# Power_Control.net
KiCad netlist of a schematic drawn in Altium Designer
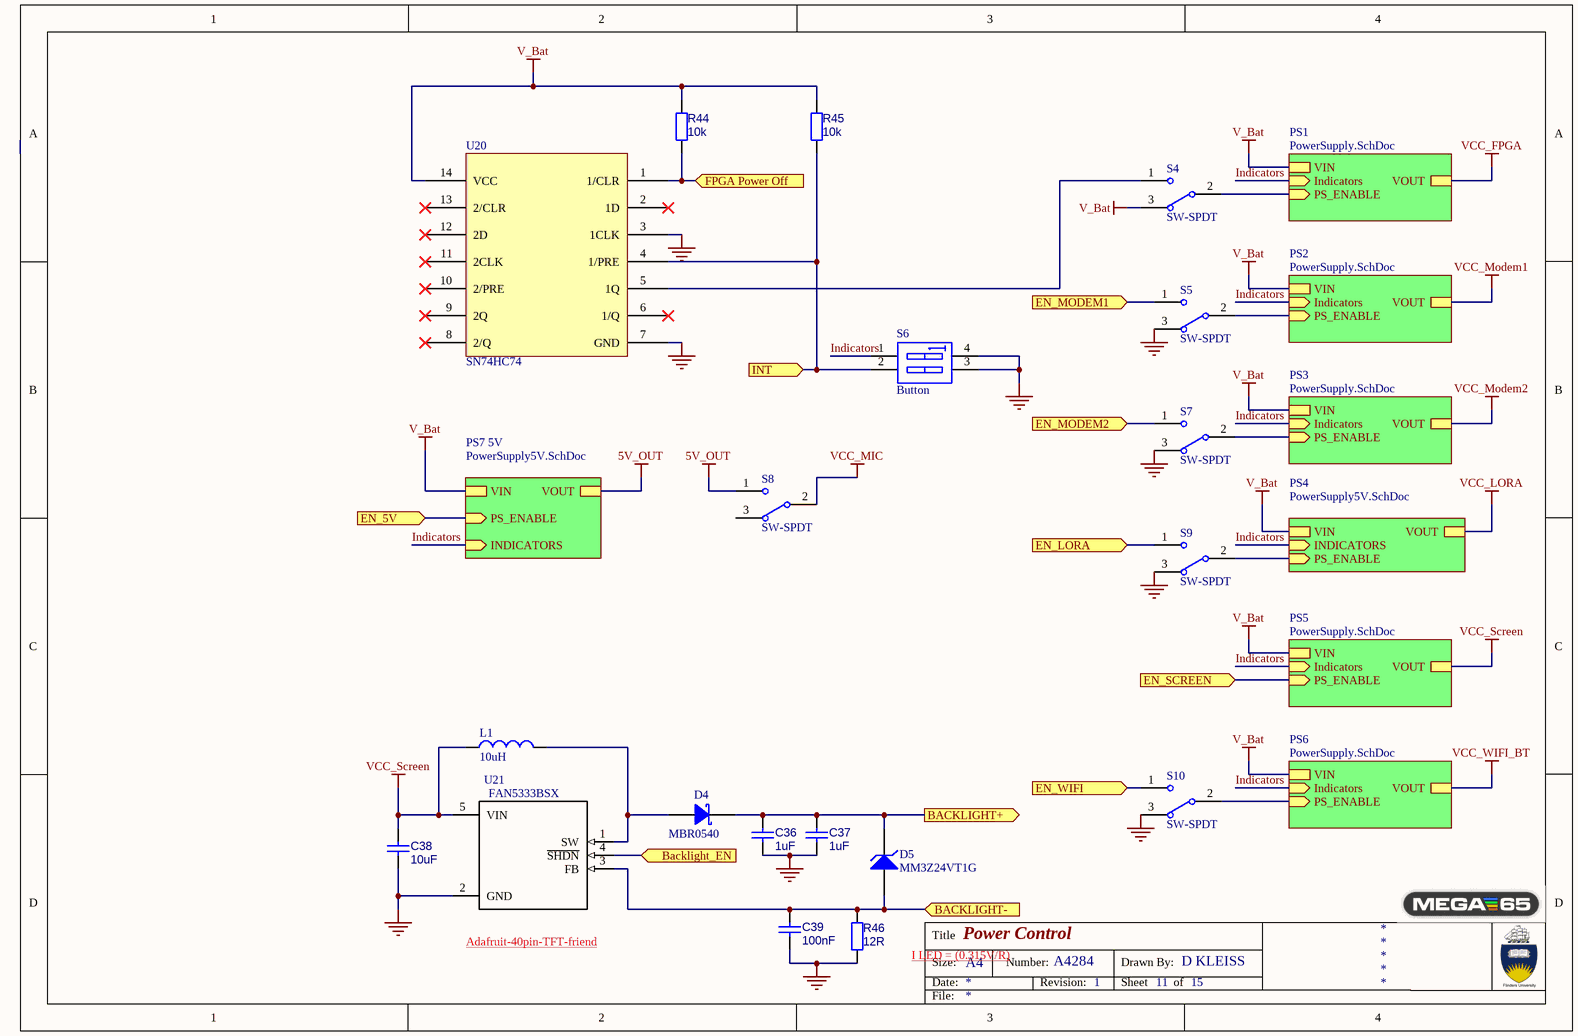
[diagram p0: Power Control.SchDoc]

(export (version "E")
  (design (tool "Eeschema 10.0.6"))
  (components
    (comp (ref "C36")
      (value "1uF")
      (footprint "0603_CAP UF HD")
      (description "Capacitor")
      (fields (field (name "MANUFACTURER") "Samsung"))
      (libsource (lib "Workshop Library 2010_06_24") (part "Cap"))
    )
    (comp (ref "C37")
      (value "1uF")
      (footprint "0603_CAP UF HD")
      (description "Capacitor")
      (fields (field (name "MANUFACTURER") "Samsung"))
      (libsource (lib "Workshop Library 2010_06_24") (part "Cap"))
    )
    (comp (ref "C38")
      (value "10uF")
      (footprint "0603_CAP UF HD")
      (description "Capacitor")
      (fields (field (name "MANUFACTURER") "Murata"))
      (libsource (lib "Workshop Library 2010_06_24") (part "Cap"))
    )
    (comp (ref "C39")
      (value "100nF")
      (footprint "0603_CAP UF HD")
      (description "Capacitor")
      (libsource (lib "Workshop Library 2010_06_24") (part "Cap"))
    )
    (comp (ref "D4")
      (value "MBR0540")
      (footprint "ONSC-SOD-123-2-425-04_V")
      (description "Diode")
      (fields (field (name "MANUFACTURER") "ON Semiconductor"))
      (libsource (lib "Workshop Library 2010_06_24") (part "DIODE_SCHOTTKY"))
    )
    (comp (ref "D5")
      (value "MM3Z24VT1G")
      (footprint "ONSC-SOD-323-2-477-02_V")
      (description "Zener Diode")
      (fields (field (name "MANUFACTURER") "ON Semiconductor"))
      (libsource (lib "Workshop Library 2010_06_24") (part "ZENER DIODE"))
    )
    (comp (ref "L1")
      (value "10uH")
      (footprint "TDK-SLF-6025-2_V")
      (description "Inductor")
      (fields (field (name "MANUFACTURER") "TDK"))
      (libsource (lib "Workshop Library 2010_06_24") (part "Inductor"))
    )
    (comp (ref "R44")
      (value "10k")
      (footprint "0603-RESISTOR HD")
      (description "Resistor")
      (libsource (lib "MEGAphone") (part "Resistor"))
    )
    (comp (ref "R45")
      (value "10k")
      (footprint "0603-RESISTOR HD")
      (description "Resistor")
      (libsource (lib "MEGAphone") (part "Resistor"))
    )
    (comp (ref "R46")
      (value "12R")
      (footprint "0805 Reflow")
      (description "Resistor")
      (libsource (lib "Workshop Library 2010_06_24") (part "Resistor"))
    )
    (comp (ref "S4")
      (value "SW-SPDT")
      (footprint "Switch SPDT OS102011MA1Q")
      (description "SPDT Subminiature Toggle Switch, Right Angle Mounting, Vertical Actuation")
      (fields
        (field (name "ELEMENT 14 PART NUMBER") "1201431")
        (field (name "MANUFACTURER") "C & K COMPONENTS")
      )
      (libsource (lib "Miscellaneous Devices") (part "SW-SPDT"))
    )
    (comp (ref "S5")
      (value "SW-SPDT")
      (footprint "Switch SPDT OS102011MA1Q")
      (description "SPDT Subminiature Toggle Switch, Right Angle Mounting, Vertical Actuation")
      (fields
        (field (name "ELEMENT 14 PART NUMBER") "1201431")
        (field (name "MANUFACTURER") "C & K COMPONENTS")
      )
      (libsource (lib "Miscellaneous Devices") (part "SW-SPDT"))
    )
    (comp (ref "S6")
      (value "Button")
      (footprint "Buttons Gameboy v2")
      (description "DIP Switch, 2 Position, SPST")
      (libsource (lib "Miscellaneous Devices") (part "SW DIP-2"))
    )
    (comp (ref "S7")
      (value "SW-SPDT")
      (footprint "Switch SPDT OS102011MA1Q")
      (description "SPDT Subminiature Toggle Switch, Right Angle Mounting, Vertical Actuation")
      (fields
        (field (name "ELEMENT 14 PART NUMBER") "1201431")
        (field (name "MANUFACTURER") "C & K COMPONENTS")
      )
      (libsource (lib "Miscellaneous Devices") (part "SW-SPDT"))
    )
    (comp (ref "S8")
      (value "SW-SPDT")
      (footprint "Switch SPDT OS102011MA1Q")
      (description "SPDT Subminiature Toggle Switch, Right Angle Mounting, Vertical Actuation")
      (fields
        (field (name "ELEMENT 14 PART NUMBER") "1201431")
        (field (name "MANUFACTURER") "C & K COMPONENTS")
      )
      (libsource (lib "Miscellaneous Devices") (part "SW-SPDT"))
    )
    (comp (ref "S9")
      (value "SW-SPDT")
      (footprint "Switch SPDT OS102011MA1Q")
      (description "SPDT Subminiature Toggle Switch, Right Angle Mounting, Vertical Actuation")
      (fields
        (field (name "ELEMENT 14 PART NUMBER") "1201431")
        (field (name "MANUFACTURER") "C & K COMPONENTS")
      )
      (libsource (lib "Miscellaneous Devices") (part "SW-SPDT"))
    )
    (comp (ref "S10")
      (value "SW-SPDT")
      (footprint "Switch SPDT OS102011MA1Q")
      (description "SPDT Subminiature Toggle Switch, Right Angle Mounting, Vertical Actuation")
      (fields
        (field (name "ELEMENT 14 PART NUMBER") "1201431")
        (field (name "MANUFACTURER") "C & K COMPONENTS")
      )
      (libsource (lib "Miscellaneous Devices") (part "SW-SPDT"))
    )
    (comp (ref "U20")
      (value "SN74HC74")
      (footprint "MEGAphone:SOIC-14")
      (fields (field (name "MANUFACTURER") "Texas Instruments"))
      (libsource (lib "MEGAphone") (part "SN74HC74"))
    )
    (comp (ref "U21")
      (value "FAN5333BSX")
      (footprint "SOT-23-5")
      (description "FAN5333B Series 5.5 V 1.5 MHz High Efficiency High Current Serial LED Driver")
      (fields (field (name "MANUFACTURER") "ON Semiconductor"))
      (libsource (lib "FAN5333BSX") (part "FAN5333BSX"))
    )
  )
  (nets
    (net (code "1") (name "/BACKLIGHT+") (class "Default")
      (node (ref "C36") (pin "1") (pinfunction "1_1") (pintype "passive"))
      (node (ref "C37") (pin "1") (pinfunction "1_1") (pintype "passive"))
      (node (ref "D4") (pin "2") (pinfunction "K_2") (pintype "passive"))
      (node (ref "D5") (pin "3") (pinfunction "K_3") (pintype "passive"))
    )
    (net (code "2") (name "/BACKLIGHT-") (class "Default")
      (node (ref "C39") (pin "1") (pinfunction "1_1") (pintype "passive"))
      (node (ref "D5") (pin "1") (pinfunction "A_1") (pintype "passive"))
      (node (ref "R46") (pin "1") (pinfunction "1_1") (pintype "passive"))
      (node (ref "U21") (pin "3") (pinfunction "FB_3") (pintype "input"))
    )
    (net (code "3") (name "/Backlight_EN") (class "Default")
      (node (ref "U21") (pin "4") (pinfunction "~{SHDN}_4") (pintype "input"))
    )
    (net (code "5") (name "/EN_LORA") (class "Default")
      (node (ref "S9") (pin "1") (pinfunction "1_1") (pintype "passive"))
    )
    (net (code "6") (name "/EN_MODEM1") (class "Default")
      (node (ref "S5") (pin "1") (pinfunction "1_1") (pintype "passive"))
    )
    (net (code "7") (name "/EN_MODEM2") (class "Default")
      (node (ref "S7") (pin "1") (pinfunction "1_1") (pintype "passive"))
    )
    (net (code "9") (name "/EN_WIFI") (class "Default")
      (node (ref "S10") (pin "1") (pinfunction "1_1") (pintype "passive"))
    )
    (net (code "10") (name "/FPGA Power Off") (class "Default")
      (node (ref "R44") (pin "2") (pinfunction "2_2") (pintype "passive"))
      (node (ref "U20") (pin "1") (pinfunction "1/CLR_1") (pintype "passive"))
    )
    (net (code "11") (name "/INT") (class "Default")
      (node (ref "R45") (pin "2") (pinfunction "2_2") (pintype "passive"))
      (node (ref "S6") (pin "2") (pinfunction "A2_2") (pintype "passive"))
      (node (ref "U20") (pin "4") (pinfunction "1/PRE_4") (pintype "passive"))
    )
    (net (code "12") (name "/Indicators") (class "Default")
      (node (ref "S6") (pin "1") (pinfunction "A1_1") (pintype "passive"))
    )
    (net (code "13") (name "/PS_ENABLE") (class "Default")
      (node (ref "S7") (pin "2") (pinfunction "2_2") (pintype "power_in"))
    )
    (net (code "14") (name "/PS_ENABLE_1") (class "Default")
      (node (ref "S10") (pin "2") (pinfunction "2_2") (pintype "power_in"))
    )
    (net (code "15") (name "/PS_ENABLE_2") (class "Default")
      (node (ref "S9") (pin "2") (pinfunction "2_2") (pintype "power_in"))
    )
    (net (code "16") (name "/PS_ENABLE_3") (class "Default")
      (node (ref "S5") (pin "2") (pinfunction "2_2") (pintype "power_in"))
    )
    (net (code "17") (name "/PS_ENABLE_4") (class "Default")
      (node (ref "S4") (pin "2") (pinfunction "2_2") (pintype "power_in"))
    )
    (net (code "18") (name "5V_OUT") (class "Default")
      (node (ref "S8") (pin "1") (pinfunction "1_1") (pintype "passive"))
    )
    (net (code "19") (name "GND") (class "Default")
      (node (ref "C36") (pin "2") (pinfunction "2_2") (pintype "passive"))
      (node (ref "C37") (pin "2") (pinfunction "2_2") (pintype "passive"))
      (node (ref "C38") (pin "2") (pinfunction "2_2") (pintype "passive"))
      (node (ref "C39") (pin "2") (pinfunction "2_2") (pintype "passive"))
      (node (ref "R46") (pin "2") (pinfunction "2_2") (pintype "passive"))
      (node (ref "S10") (pin "3") (pinfunction "3_3") (pintype "passive"))
      (node (ref "S5") (pin "3") (pinfunction "3_3") (pintype "passive"))
      (node (ref "S6") (pin "3") (pinfunction "B2_3") (pintype "passive"))
      (node (ref "S6") (pin "4") (pinfunction "B1_4") (pintype "passive"))
      (node (ref "S7") (pin "3") (pinfunction "3_3") (pintype "passive"))
      (node (ref "S9") (pin "3") (pinfunction "3_3") (pintype "passive"))
      (node (ref "U20") (pin "3") (pinfunction "1CLK_3") (pintype "passive"))
      (node (ref "U20") (pin "7") (pinfunction "GND_7") (pintype "passive"))
      (node (ref "U21") (pin "2") (pinfunction "GND_2") (pintype "power_in"))
    )
    (net (code "20") (name "Net-(D4-A)") (class "Default")
      (node (ref "D4") (pin "1") (pinfunction "A_1") (pintype "passive"))
      (node (ref "L1") (pin "2") (pinfunction "2_2") (pintype "passive"))
      (node (ref "U21") (pin "1") (pinfunction "SW_1") (pintype "input"))
    )
    (net (code "21") (name "Net-(U20-1Q)") (class "Default")
      (node (ref "S4") (pin "1") (pinfunction "1_1") (pintype "passive"))
      (node (ref "U20") (pin "5") (pinfunction "1Q_5") (pintype "passive"))
    )
    (net (code "24") (name "VCC_MIC") (class "Default")
      (node (ref "S8") (pin "2") (pinfunction "2_2") (pintype "power_in"))
    )
    (net (code "27") (name "VCC_Screen") (class "Default")
      (node (ref "C38") (pin "1") (pinfunction "1_1") (pintype "passive"))
      (node (ref "L1") (pin "1") (pinfunction "1_1") (pintype "passive"))
      (node (ref "U21") (pin "5") (pinfunction "VIN_5") (pintype "power_in"))
    )
    (net (code "29") (name "V_Bat") (class "Default")
      (node (ref "R44") (pin "1") (pinfunction "1_1") (pintype "passive"))
      (node (ref "R45") (pin "1") (pinfunction "1_1") (pintype "passive"))
      (node (ref "S4") (pin "3") (pinfunction "3_3") (pintype "passive"))
      (node (ref "U20") (pin "14") (pinfunction "VCC_14") (pintype "passive"))
    )
    (net (code "30") (name "unconnected-(S8-Pad3)") (class "Default")
      (node (ref "S8") (pin "3") (pinfunction "3_3") (pintype "passive"))
    )
    (net (code "31") (name "unconnected-(U20-1D-Pad2)") (class "Default")
      (node (ref "U20") (pin "2") (pinfunction "1D_2") (pintype "passive+no_connect"))
    )
    (net (code "32") (name "unconnected-(U20-1{slash}Q-Pad6)") (class "Default")
      (node (ref "U20") (pin "6") (pinfunction "1/Q_6") (pintype "passive+no_connect"))
    )
    (net (code "33") (name "unconnected-(U20-2CLK-Pad11)") (class "Default")
      (node (ref "U20") (pin "11") (pinfunction "2CLK_11") (pintype "passive+no_connect"))
    )
    (net (code "34") (name "unconnected-(U20-2D-Pad12)") (class "Default")
      (node (ref "U20") (pin "12") (pinfunction "2D_12") (pintype "passive+no_connect"))
    )
    (net (code "35") (name "unconnected-(U20-2Q-Pad9)") (class "Default")
      (node (ref "U20") (pin "9") (pinfunction "2Q_9") (pintype "passive+no_connect"))
    )
    (net (code "36") (name "unconnected-(U20-2{slash}CLR-Pad13)") (class "Default")
      (node (ref "U20") (pin "13") (pinfunction "2/CLR_13") (pintype "passive+no_connect"))
    )
    (net (code "37") (name "unconnected-(U20-2{slash}PRE-Pad10)") (class "Default")
      (node (ref "U20") (pin "10") (pinfunction "2/PRE_10") (pintype "passive+no_connect"))
    )
    (net (code "38") (name "unconnected-(U20-2{slash}Q-Pad8)") (class "Default")
      (node (ref "U20") (pin "8") (pinfunction "2/Q_8") (pintype "passive+no_connect"))
    )
  )
)
